# delorean.net
KiCad netlist of a schematic drawn in EAGLE
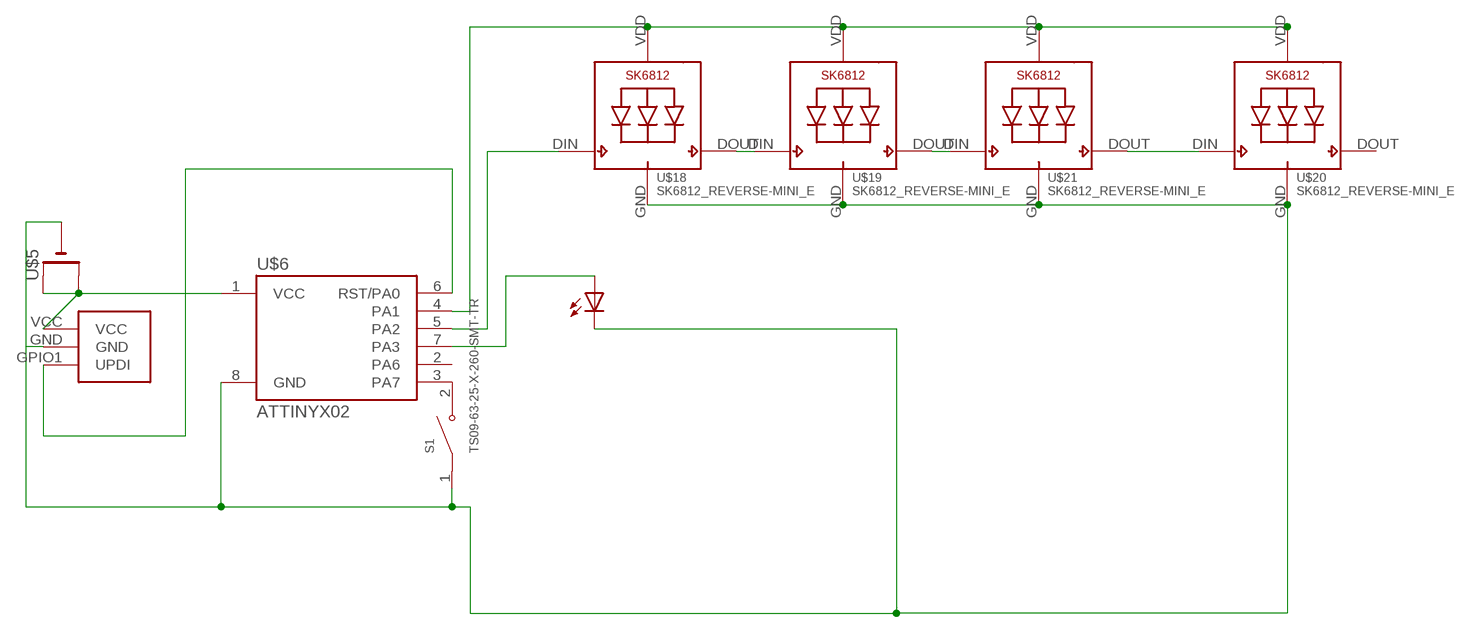
[diagram p0: schematic, sheet 1]

(export (version "E")
  (design (tool "Eeschema 10.0.6"))
  (components
    (comp (ref "S1")
      (value "TS09-63-25-X-260-SMT-TR")
      (footprint "eagle-import:SW_TS09-63-25-X-260-SMT-TR")
      (fields (field (name "MANUFACTURER") "CUI Devices"))
      (libsource (lib "eagle-import") (part "TS09-63-25-X-260-SMT-TR"))
    )
    (comp (ref "U$1")
      (value "LED_SMD_REVERSEMOUNT3528")
      (footprint "eagle-import:B_3528-21R")
      (libsource (lib "eagle-import") (part "LED_SMD_REVERSEMOUNT3528"))
    )
    (comp (ref "U$5")
      (value "CR2032SMT")
      (footprint "eagle-import:CR2032-SMD")
      (libsource (lib "eagle-import") (part "CR2032SMT"))
    )
    (comp (ref "U$6")
      (value "ATTINYX02")
      (footprint "eagle-import:SOIC08_JEDEC_150MIL")
      (libsource (lib "eagle-import") (part "ATTINYX02"))
    )
    (comp (ref "U$7")
      (value "SAO")
      (footprint "eagle-import:SAO_SMD")
      (libsource (lib "eagle-import") (part "SAO"))
    )
    (comp (ref "U$18")
      (value "SK6812_REVERSE-MINI_E")
      (footprint "eagle-import:SK6812-MINI-E")
      (libsource (lib "eagle-import") (part "SK6812_REVERSE-MINI_E"))
    )
    (comp (ref "U$19")
      (value "SK6812_REVERSE-MINI_E")
      (footprint "eagle-import:SK6812-MINI-E")
      (libsource (lib "eagle-import") (part "SK6812_REVERSE-MINI_E"))
    )
    (comp (ref "U$20")
      (value "SK6812_REVERSE-MINI_E")
      (footprint "eagle-import:SK6812-MINI-E")
      (libsource (lib "eagle-import") (part "SK6812_REVERSE-MINI_E"))
    )
    (comp (ref "U$21")
      (value "SK6812_REVERSE-MINI_E")
      (footprint "eagle-import:SK6812-MINI-E")
      (libsource (lib "eagle-import") (part "SK6812_REVERSE-MINI_E"))
    )
  )
  (nets
    (net (code "1") (name "Net-(U$1-A)") (class "Default")
      (node (ref "U$1") (pin "-") (pinfunction "A_-") (pintype "passive"))
      (node (ref "U$6") (pin "7") (pinfunction "PA3_7") (pintype "bidirectional"))
    )
    (net (code "2") (name "Net-(U$1-C)") (class "Default")
      (node (ref "S1") (pin "1") (pinfunction "1_1") (pintype "passive"))
      (node (ref "U$1") (pin "+") (pinfunction "C_+") (pintype "passive"))
      (node (ref "U$18") (pin "GND") (pinfunction "GND_GND") (pintype "power_in"))
      (node (ref "U$19") (pin "GND") (pinfunction "GND_GND") (pintype "power_in"))
      (node (ref "U$20") (pin "GND") (pinfunction "GND_GND") (pintype "power_in"))
      (node (ref "U$21") (pin "GND") (pinfunction "GND_GND") (pintype "power_in"))
      (node (ref "U$5") (pin "-") (pinfunction "-_-") (pintype "passive"))
      (node (ref "U$6") (pin "8") (pinfunction "GND_8") (pintype "power_in"))
      (node (ref "U$7") (pin "GND") (pinfunction "GND_GND") (pintype "bidirectional"))
    )
    (net (code "3") (name "Net-(U$5-+)") (class "Default")
      (node (ref "U$5") (pin "+$1") (pinfunction "+_+$1") (pintype "passive"))
      (node (ref "U$5") (pin "+$2") (pinfunction "+1_+$2") (pintype "passive"))
      (node (ref "U$6") (pin "1") (pinfunction "VCC_1") (pintype "power_in"))
      (node (ref "U$7") (pin "VCC") (pinfunction "VCC_VCC") (pintype "bidirectional"))
    )
    (net (code "4") (name "Net-(U$6-PA1)") (class "Default")
      (node (ref "U$18") (pin "VDD") (pinfunction "VDD_VDD") (pintype "power_in"))
      (node (ref "U$19") (pin "VDD") (pinfunction "VDD_VDD") (pintype "power_in"))
      (node (ref "U$20") (pin "VDD") (pinfunction "VDD_VDD") (pintype "power_in"))
      (node (ref "U$21") (pin "VDD") (pinfunction "VDD_VDD") (pintype "power_in"))
      (node (ref "U$6") (pin "4") (pinfunction "PA1_4") (pintype "bidirectional"))
    )
    (net (code "5") (name "Net-(U$6-PA7)") (class "Default")
      (node (ref "S1") (pin "2") (pinfunction "2_2") (pintype "passive"))
      (node (ref "U$6") (pin "3") (pinfunction "PA7_3") (pintype "bidirectional"))
    )
    (net (code "6") (name "Net-(U$6-RST{slash}PA0)") (class "Default")
      (node (ref "U$6") (pin "6") (pinfunction "RST/PA0_6") (pintype "bidirectional"))
      (node (ref "U$7") (pin "GPIO1") (pinfunction "UPDI_GPIO1") (pintype "bidirectional"))
    )
    (net (code "7") (name "Net-(U$18-DI)") (class "Default")
      (node (ref "U$18") (pin "DIN") (pinfunction "DI_DIN") (pintype "input"))
      (node (ref "U$6") (pin "5") (pinfunction "PA2_5") (pintype "bidirectional"))
    )
    (net (code "8") (name "Net-(U$18-DO)") (class "Default")
      (node (ref "U$18") (pin "DOUT") (pinfunction "DO_DOUT") (pintype "output"))
      (node (ref "U$19") (pin "DIN") (pinfunction "DI_DIN") (pintype "input"))
    )
    (net (code "9") (name "Net-(U$19-DO)") (class "Default")
      (node (ref "U$19") (pin "DOUT") (pinfunction "DO_DOUT") (pintype "output"))
      (node (ref "U$21") (pin "DIN") (pinfunction "DI_DIN") (pintype "input"))
    )
    (net (code "10") (name "Net-(U$20-DI)") (class "Default")
      (node (ref "U$20") (pin "DIN") (pinfunction "DI_DIN") (pintype "input"))
      (node (ref "U$21") (pin "DOUT") (pinfunction "DO_DOUT") (pintype "output"))
    )
    (net (code "11") (name "unconnected-(U$6-PA6-Pad2)") (class "Default")
      (node (ref "U$6") (pin "2") (pinfunction "PA6_2") (pintype "bidirectional"))
    )
    (net (code "12") (name "unconnected-(U$20-DO-PadDOUT)") (class "Default")
      (node (ref "U$20") (pin "DOUT") (pinfunction "DO_DOUT") (pintype "output"))
    )
  )
)
